# Pressure_Transducer.net
KiCad netlist of a schematic drawn in Altium Designer
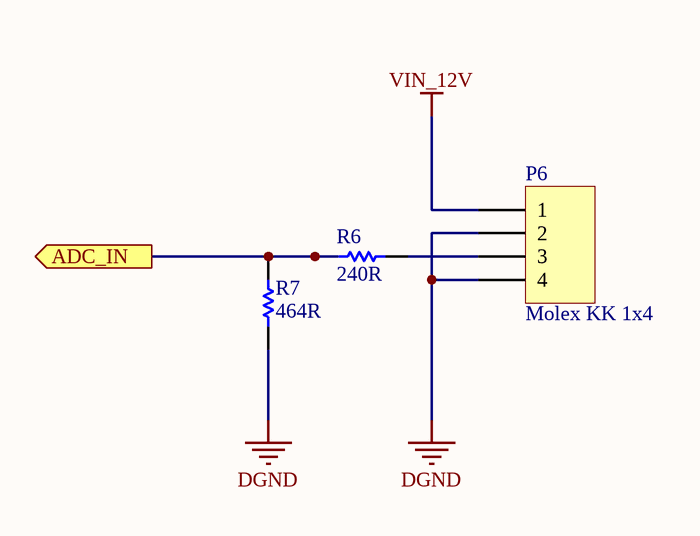
[diagram p0: Pressure_Transducer.SchDoc]

(export (version "E")
  (design (tool "Eeschema 10.0.6"))
  (components
    (comp (ref "P6")
      (value "Molex KK 1x4")
      (footprint "Molex KK 4x1")
      (description "1x4 Molex KK Connector")
      (libsource (lib "PARSEC") (part "Molex KK 1x4"))
    )
    (comp (ref "R6")
      (value "240R")
      (footprint "R0805")
      (description "RESISTOR 0805")
      (libsource (lib "PARSEC") (part "R0805"))
    )
    (comp (ref "R7")
      (value "464R")
      (footprint "R0805")
      (description "RESISTOR 0805")
      (libsource (lib "PARSEC") (part "R0805"))
    )
  )
  (nets
    (net (code "1") (name "/ADC_IN") (class "Default")
      (node (ref "R6") (pin "2") (pinfunction "2_2") (pintype "passive"))
      (node (ref "R7") (pin "2") (pinfunction "2_2") (pintype "passive"))
    )
    (net (code "2") (name "DGND") (class "Default")
      (node (ref "P6") (pin "2") (pinfunction "2_2") (pintype "passive"))
      (node (ref "P6") (pin "4") (pinfunction "4_4") (pintype "passive"))
      (node (ref "R7") (pin "1") (pinfunction "1_1") (pintype "passive"))
    )
    (net (code "3") (name "Net-(P6-Pad3)") (class "Default")
      (node (ref "P6") (pin "3") (pinfunction "3_3") (pintype "passive"))
      (node (ref "R6") (pin "1") (pinfunction "1_1") (pintype "passive"))
    )
    (net (code "4") (name "VIN_12V") (class "Default")
      (node (ref "P6") (pin "1") (pinfunction "1_1") (pintype "passive"))
    )
  )
)
